# T_Phase_Sense_Signal_Isolation.net
KiCad netlist of a schematic drawn in Altium Designer
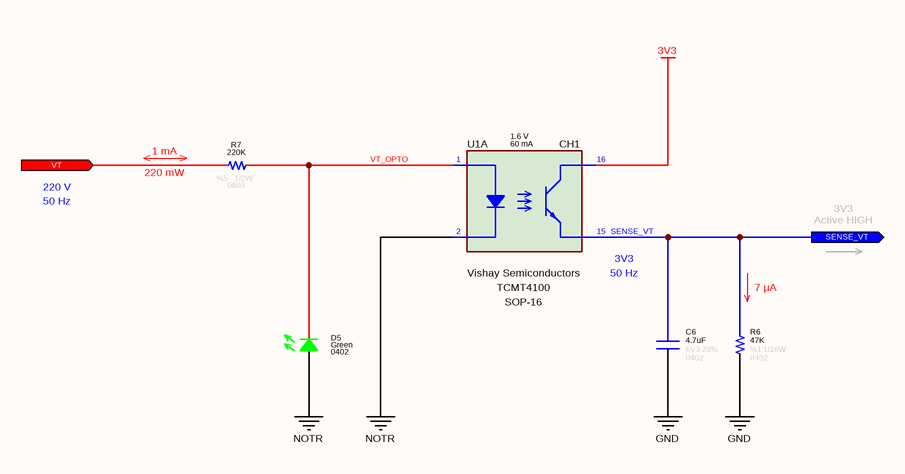
[diagram p0: T Phase Sense Signal Isolation.SchDoc]

(export (version "E")
  (design (tool "Eeschema 10.0.6"))
  (components
    (comp (ref "C6")
      (value "4.7uF")
      (footprint "CAPACITOR_0402")
      (description "Multilayer Ceramic Capacitors - SMD - 6V3 4.7uF X5R 0402 20%")
      (fields
        (field (name "MANUFACTURER PART NUMBER") "C0402C475M9PACTU")
        (field (name "TOLERANCE") "20%")
        (field (name "CASE") "0402")
        (field (name "VOLTAGE") "6V3")
        (field (name "Comment") "Capacitor - 4.7uF [0402] (Ceramic)")
      )
      (libsource (lib "Akkoyun") (part "Capacitor - 4.7uF [0402-6V3]"))
    )
    (comp (ref "D5")
      (value "SMD LED (Green)")
      (footprint "LED_0402")
      (description "Standard LEDs - SMD MINI-MOLD ULTRA COMPACT GREEN")
      (fields
        (field (name "MANUFACTURER PART NUMBER") "SML-P12MTT86R")
        (field (name "CASE") "0402")
        (field (name "COLOR") "Green")
      )
      (libsource (lib "Akkoyun") (part "Diode - LED (0402-Green)"))
    )
    (comp (ref "R6")
      (value "47K")
      (footprint "RESISTOR_0402")
      (description "Thick Film Resistors - SMD 1/16 W 47 KOhm 1%")
      (fields
        (field (name "MANUFACTURER PART NUMBER") "CRCW040247K0FKED")
        (field (name "TOLERANCE") "%1")
        (field (name "CASE") "0402")
        (field (name "POWER") "1/16W")
        (field (name "Comment") "47K - 0402 - %1 - 1/16W")
      )
      (libsource (lib "Akkoyun") (part "Resistor - 47K [0402]"))
    )
    (comp (ref "R7")
      (value "220K")
      (footprint "RESISTOR_0805")
      (description "Thick Film Resistors - SMD 1/2 W 220 KOhm 5%")
      (fields
        (field (name "MANUFACTURER PART NUMBER") "CRCW0805220KJNEAHP")
        (field (name "CASE") "0805")
        (field (name "TOLERANCE") "%5")
        (field (name "POWER") "1/2W")
        (field (name "Comment") "220K - 0805 - %5 - 1/16W")
      )
      (libsource (lib "Akkoyun") (part "Resistor - 220K [0805]"))
    )
    (comp (ref "U1")
      (value "TCMT4100")
      (footprint "SO-16")
      (description "OptpCoupler 4CH 16 Pin (SOP16)")
      (fields
        (field (name "IF - FORWARD CURRENT") "60 mA")
        (field (name "VF - FORWARD VOLTAGE") "1.6 V")
        (field (name "MANUFACTURER NAME") "Vishay Semiconductors")
        (field (name "MANUFACTURER PART NUMBER") "TCMT4100")
        (field (name "CASE") "SOP-16")
      )
      (libsource (lib "Akkoyun") (part "IC - TCMT4100"))
    )
  )
  (nets
    (net (code "1") (name "/SENSE_VT") (class "Default")
      (node (ref "C6") (pin "2") (pinfunction "2_2") (pintype "passive"))
      (node (ref "R6") (pin "2") (pinfunction "2_2") (pintype "passive"))
      (node (ref "U1") (pin "15") (pinfunction "Emiter_CH1_15") (pintype "open_emitter"))
    )
    (net (code "2") (name "/VT") (class "Default")
      (node (ref "R7") (pin "2") (pinfunction "2_2") (pintype "passive"))
    )
    (net (code "3") (name "/VT_OPTO") (class "Default")
      (node (ref "D5") (pin "1") (pinfunction "1_1") (pintype "passive"))
      (node (ref "R7") (pin "1") (pinfunction "1_1") (pintype "passive"))
      (node (ref "U1") (pin "1") (pinfunction "Anode_CH1_1") (pintype "passive"))
    )
    (net (code "4") (name "3V3") (class "Default")
      (node (ref "U1") (pin "16") (pinfunction "Collector_CH1_16") (pintype "passive"))
    )
    (net (code "5") (name "GND") (class "Default")
      (node (ref "C6") (pin "1") (pinfunction "1_1") (pintype "passive"))
      (node (ref "R6") (pin "1") (pinfunction "1_1") (pintype "passive"))
    )
    (net (code "6") (name "NOTR") (class "Default")
      (node (ref "D5") (pin "2") (pinfunction "2_2") (pintype "passive"))
      (node (ref "U1") (pin "2") (pinfunction "Cathode_CH1_2") (pintype "passive"))
    )
  )
)
